# tritiled22_cr2354.net
KiCad netlist of a schematic drawn in EAGLE
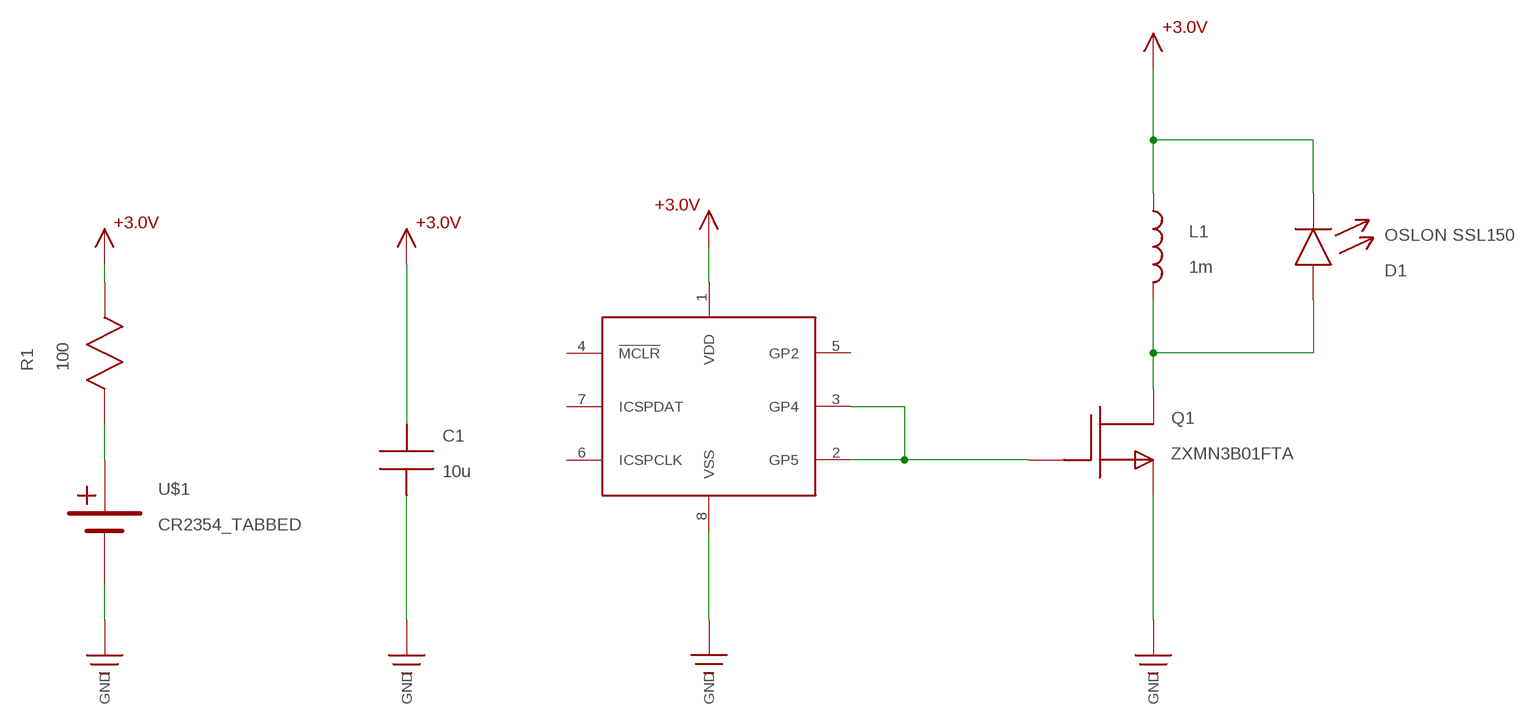
[diagram p0: schematic, sheet 1]

(export (version "E")
  (design (tool "Eeschema 10.0.6"))
  (components
    (comp (ref "C1")
      (value "10u")
      (footprint "eagle-import:1206")
      (libsource (lib "eagle-import") (part "C1206"))
    )
    (comp (ref "D1")
      (value "OSLON SSL150")
      (footprint "eagle-import:OSLON_3030_LED")
      (libsource (lib "eagle-import") (part "LEDSSL150"))
    )
    (comp (ref "L1")
      (value "1m")
      (footprint "eagle-import:SRR6028_INDUCTOR")
      (libsource (lib "eagle-import") (part "SRR6028_INDUCTOR"))
    )
    (comp (ref "Q1")
      (value "ZXMN3B01FTA")
      (footprint "eagle-import:SOT-23")
      (libsource (lib "eagle-import") (part "ZXMN3B01FSOT23"))
    )
    (comp (ref "R1")
      (value "100")
      (footprint "eagle-import:R1206")
      (libsource (lib "eagle-import") (part "R1206"))
    )
    (comp (ref "U$1")
      (value "CR2354_TABBED")
      (footprint "eagle-import:CR2354_TABBED")
      (libsource (lib "eagle-import") (part "CR2354_TABBED"))
    )
    (comp (ref "U1")
      (value "PIC12LF1571")
      (footprint "eagle-import:SOIC8")
      (libsource (lib "eagle-import") (part "PIC12LF1571"))
    )
  )
  (nets
    (net (code "1") (name "+3.0V") (class "Default")
      (node (ref "C1") (pin "P$1") (pinfunction "P$1_P$1") (pintype "bidirectional"))
      (node (ref "D1") (pin "C") (pinfunction "C_C") (pintype "bidirectional"))
      (node (ref "L1") (pin "P$1") (pinfunction "1_P$1") (pintype "passive"))
      (node (ref "R1") (pin "P$2") (pinfunction "P$2_P$2") (pintype "bidirectional"))
      (node (ref "U1") (pin "1") (pinfunction "VDD_1") (pintype "bidirectional"))
    )
    (net (code "2") (name "GND") (class "Default")
      (node (ref "C1") (pin "P$2") (pinfunction "P$2_P$2") (pintype "bidirectional"))
      (node (ref "Q1") (pin "2") (pinfunction "S_2") (pintype "bidirectional"))
      (node (ref "U$1") (pin "GND") (pinfunction "0V_GND") (pintype "power_in"))
      (node (ref "U1") (pin "8") (pinfunction "VSS_8") (pintype "bidirectional"))
    )
    (net (code "3") (name "Net-(L1-2)") (class "Default")
      (node (ref "D1") (pin "A") (pinfunction "A_A") (pintype "bidirectional"))
      (node (ref "L1") (pin "P$2") (pinfunction "2_P$2") (pintype "passive"))
      (node (ref "Q1") (pin "3") (pinfunction "D_3") (pintype "bidirectional"))
    )
    (net (code "4") (name "Net-(Q1-G)") (class "Default")
      (node (ref "Q1") (pin "1") (pinfunction "G_1") (pintype "bidirectional"))
      (node (ref "U1") (pin "2") (pinfunction "GP5_2") (pintype "bidirectional"))
      (node (ref "U1") (pin "3") (pinfunction "GP4_3") (pintype "bidirectional"))
    )
    (net (code "5") (name "Net-(U$1-+V)") (class "Default")
      (node (ref "R1") (pin "P$1") (pinfunction "P$1_P$1") (pintype "bidirectional"))
      (node (ref "U$1") (pin "+3V") (pinfunction "+V_+3V") (pintype "power_in"))
    )
    (net (code "6") (name "unconnected-(U1-GP2-Pad5)") (class "Default")
      (node (ref "U1") (pin "5") (pinfunction "GP2_5") (pintype "bidirectional"))
    )
    (net (code "7") (name "unconnected-(U1-ICSPCLK-Pad6)") (class "Default")
      (node (ref "U1") (pin "6") (pinfunction "ICSPCLK_6") (pintype "bidirectional"))
    )
    (net (code "8") (name "unconnected-(U1-ICSPDAT-Pad7)") (class "Default")
      (node (ref "U1") (pin "7") (pinfunction "ICSPDAT_7") (pintype "bidirectional"))
    )
    (net (code "9") (name "unconnected-(U1-~{MCLR}-Pad4)") (class "Default")
      (node (ref "U1") (pin "4") (pinfunction "~{MCLR}_4") (pintype "bidirectional"))
    )
  )
)
